# 06-General_I2C_Devices.net
KiCad netlist of a schematic drawn in Altium Designer
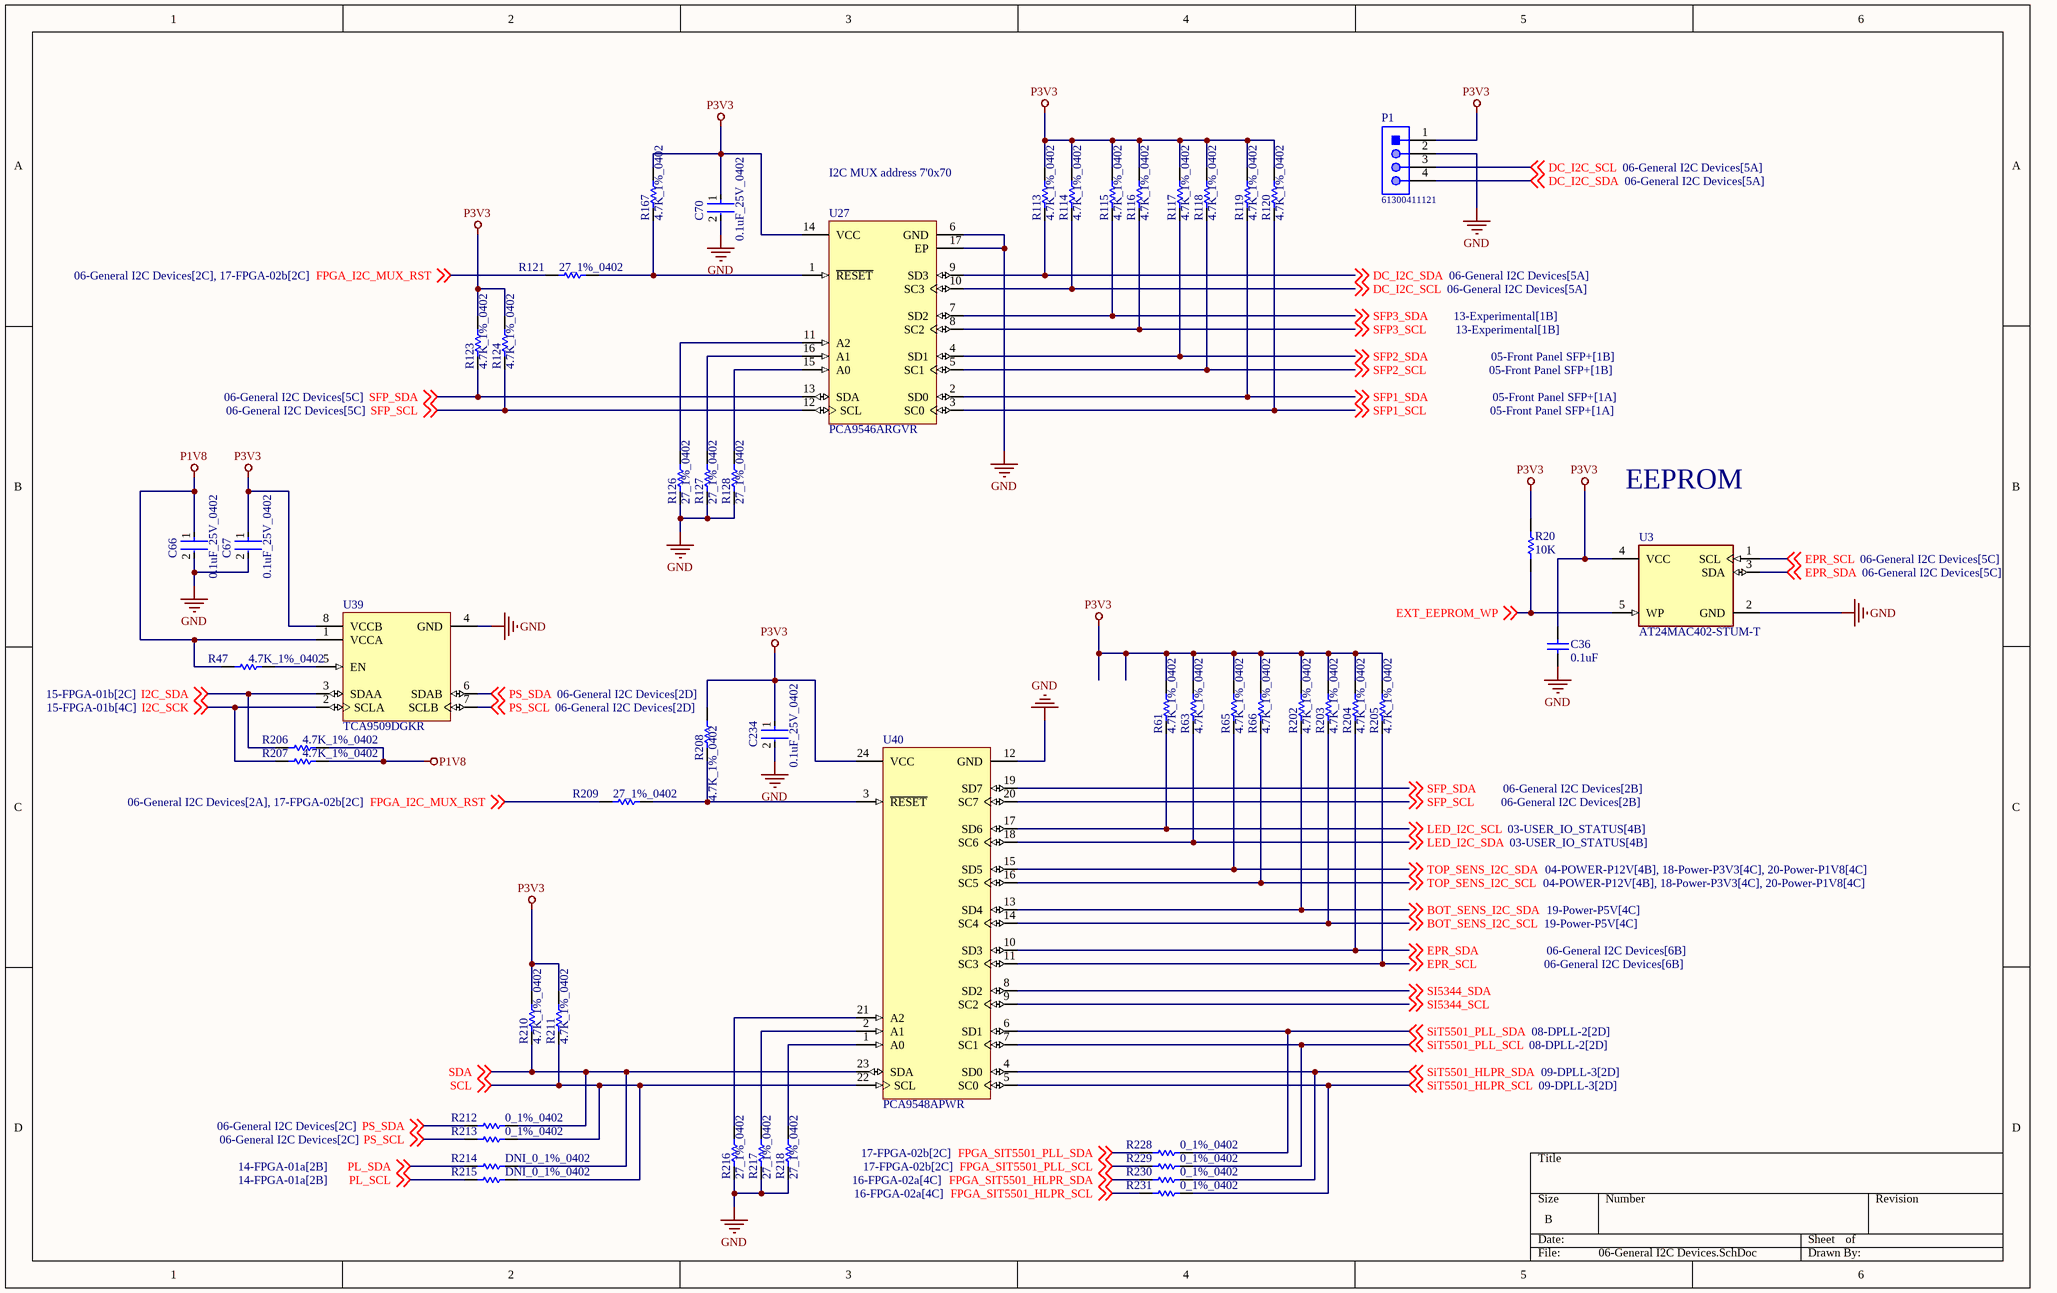
[diagram p0: 06-General I2C Devices.SchDoc]

(export (version "E")
  (design (tool "Eeschema 10.0.6"))
  (components
    (comp (ref "C36")
      (value "0.1uF")
      (footprint "CAPC1608X87X45ML20T05")
      (description "C0603X104K5RACAUTO")
      (fields (field (name "MANUFACTURER") "Kemet"))
      (libsource (lib "Altium Content Vault") (part "CAP"))
    )
    (comp (ref "C66")
      (value "0.1uF_25V_0402")
      (footprint "FP-0402-L_1_0_1-W_0_5_0_1-IPC_C")
      (description "General Purpose Ceramic Capacitor, 0402, 100nF, 10%, X7R, 15%, 25V")
      (fields (field (name "VOLTAGE") "25V") (field (name "TOLERANCE") "10%"))
      (libsource (lib "Altium Content Vault") (part "b4654b650e69147ec39a6b967a45e02"))
    )
    (comp (ref "C67")
      (value "0.1uF_25V_0402")
      (footprint "FP-0402-L_1_0_1-W_0_5_0_1-IPC_C")
      (description "General Purpose Ceramic Capacitor, 0402, 100nF, 10%, X7R, 15%, 25V")
      (fields (field (name "VOLTAGE") "25V") (field (name "TOLERANCE") "10%"))
      (libsource (lib "Altium Content Vault") (part "b4654b650e69147ec39a6b967a45e02"))
    )
    (comp (ref "C70")
      (value "0.1uF_25V_0402")
      (footprint "FP-0402-L_1_0_1-W_0_5_0_1-IPC_C")
      (description "General Purpose Ceramic Capacitor, 0402, 100nF, 10%, X7R, 15%, 25V")
      (fields (field (name "VOLTAGE") "25V") (field (name "TOLERANCE") "10%"))
      (libsource (lib "Altium Content Vault") (part "b4654b650e69147ec39a6b967a45e02"))
    )
    (comp (ref "C234")
      (value "0.1uF_25V_0402")
      (footprint "FP-0402-L_1_0_1-W_0_5_0_1-IPC_C")
      (description "General Purpose Ceramic Capacitor, 0402, 100nF, 10%, X7R, 15%, 25V")
      (fields (field (name "VOLTAGE") "25V") (field (name "TOLERANCE") "10%"))
      (libsource (lib "Altium Content Vault") (part "b4654b650e69147ec39a6b967a45e02"))
    )
    (comp (ref "P1")
      (value "61300411121")
      (footprint "61300411121")
      (description "THT Vertical Pin Header WR-PHD, Pitch 2.54 mm, Single Row, 4 pins")
      (fields (field (name "MANUFACTURER") "Wurth Elektronik") (field (name "PUBLISHER") "WurthElektronik"))
      (libsource (lib "Altium Content Vault") (part "WE-CN-1P-M-R4"))
    )
    (comp (ref "R20")
      (value "10K")
      (footprint "RESC1608X55X30LL15T20")
      (fields (field (name "TOLERANCE") "±1%") (field (name "MANUFACTURER") "Stackpole-Electronics-Inc."))
      (libsource (lib "Altium Content Vault") (part "RES-2"))
    )
    (comp (ref "R47")
      (value "4.7K_1%_0402")
      (footprint "RESC1005X40X25NL10T10")
      (fields (field (name "MANUFACTURER") "Bourns") (field (name "PART NUMBER") "CR0402-FX-4701GLF"))
      (libsource (lib "Altium Content Vault") (part "RES"))
    )
    (comp (ref "R61")
      (value "4.7K_1%_0402")
      (footprint "RESC1005X40X25NL10T10")
      (fields (field (name "MANUFACTURER") "Bourns") (field (name "PART NUMBER") "CR0402-FX-4701GLF"))
      (libsource (lib "Altium Content Vault") (part "RES"))
    )
    (comp (ref "R63")
      (value "4.7K_1%_0402")
      (footprint "RESC1005X40X25NL10T10")
      (fields (field (name "MANUFACTURER") "Bourns") (field (name "PART NUMBER") "CR0402-FX-4701GLF"))
      (libsource (lib "Altium Content Vault") (part "RES"))
    )
    (comp (ref "R65")
      (value "4.7K_1%_0402")
      (footprint "RESC1005X40X25NL10T10")
      (fields (field (name "MANUFACTURER") "Bourns") (field (name "PART NUMBER") "CR0402-FX-4701GLF"))
      (libsource (lib "Altium Content Vault") (part "RES"))
    )
    (comp (ref "R66")
      (value "4.7K_1%_0402")
      (footprint "RESC1005X40X25NL10T10")
      (fields (field (name "MANUFACTURER") "Bourns") (field (name "PART NUMBER") "CR0402-FX-4701GLF"))
      (libsource (lib "Altium Content Vault") (part "RES"))
    )
    (comp (ref "R113")
      (value "4.7K_1%_0402")
      (footprint "RESC1005X40X25NL10T10")
      (fields (field (name "MANUFACTURER") "Bourns") (field (name "PART NUMBER") "CR0402-FX-4701GLF"))
      (libsource (lib "Altium Content Vault") (part "RES"))
    )
    (comp (ref "R114")
      (value "4.7K_1%_0402")
      (footprint "RESC1005X40X25NL10T10")
      (fields (field (name "MANUFACTURER") "Bourns") (field (name "PART NUMBER") "CR0402-FX-4701GLF"))
      (libsource (lib "Altium Content Vault") (part "RES"))
    )
    (comp (ref "R115")
      (value "4.7K_1%_0402")
      (footprint "RESC1005X40X25NL10T10")
      (fields (field (name "MANUFACTURER") "Bourns") (field (name "PART NUMBER") "CR0402-FX-4701GLF"))
      (libsource (lib "Altium Content Vault") (part "RES"))
    )
    (comp (ref "R116")
      (value "4.7K_1%_0402")
      (footprint "RESC1005X40X25NL10T10")
      (fields (field (name "MANUFACTURER") "Bourns") (field (name "PART NUMBER") "CR0402-FX-4701GLF"))
      (libsource (lib "Altium Content Vault") (part "RES"))
    )
    (comp (ref "R117")
      (value "4.7K_1%_0402")
      (footprint "RESC1005X40X25NL10T10")
      (fields (field (name "MANUFACTURER") "Bourns") (field (name "PART NUMBER") "CR0402-FX-4701GLF"))
      (libsource (lib "Altium Content Vault") (part "RES"))
    )
    (comp (ref "R118")
      (value "4.7K_1%_0402")
      (footprint "RESC1005X40X25NL10T10")
      (fields (field (name "MANUFACTURER") "Bourns") (field (name "PART NUMBER") "CR0402-FX-4701GLF"))
      (libsource (lib "Altium Content Vault") (part "RES"))
    )
    (comp (ref "R119")
      (value "4.7K_1%_0402")
      (footprint "RESC1005X40X25NL10T10")
      (fields (field (name "MANUFACTURER") "Bourns") (field (name "PART NUMBER") "CR0402-FX-4701GLF"))
      (libsource (lib "Altium Content Vault") (part "RES"))
    )
    (comp (ref "R120")
      (value "4.7K_1%_0402")
      (footprint "RESC1005X40X25NL10T10")
      (fields (field (name "MANUFACTURER") "Bourns") (field (name "PART NUMBER") "CR0402-FX-4701GLF"))
      (libsource (lib "Altium Content Vault") (part "RES"))
    )
    (comp (ref "R121")
      (value "27_1%_0402")
      (footprint "RESC1005X40X25NL05T05")
      (fields (field (name "PART NUMBER") "CRCW040227R0FKED") (field (name "MANUFACTURER") "Vishay Dale"))
      (libsource (lib "Altium Content Vault") (part "RES"))
    )
    (comp (ref "R123")
      (value "4.7K_1%_0402")
      (footprint "RESC1005X40X25NL10T10")
      (fields (field (name "MANUFACTURER") "Bourns") (field (name "PART NUMBER") "CR0402-FX-4701GLF"))
      (libsource (lib "Altium Content Vault") (part "RES"))
    )
    (comp (ref "R124")
      (value "4.7K_1%_0402")
      (footprint "RESC1005X40X25NL10T10")
      (fields (field (name "MANUFACTURER") "Bourns") (field (name "PART NUMBER") "CR0402-FX-4701GLF"))
      (libsource (lib "Altium Content Vault") (part "RES"))
    )
    (comp (ref "R126")
      (value "27_1%_0402")
      (footprint "RESC1005X40X25NL05T05")
      (fields (field (name "PART NUMBER") "CRCW040227R0FKED") (field (name "MANUFACTURER") "Vishay Dale"))
      (libsource (lib "Altium Content Vault") (part "RES"))
    )
    (comp (ref "R127")
      (value "27_1%_0402")
      (footprint "RESC1005X40X25NL05T05")
      (fields (field (name "PART NUMBER") "CRCW040227R0FKED") (field (name "MANUFACTURER") "Vishay Dale"))
      (libsource (lib "Altium Content Vault") (part "RES"))
    )
    (comp (ref "R128")
      (value "27_1%_0402")
      (footprint "RESC1005X40X25NL05T05")
      (fields (field (name "PART NUMBER") "CRCW040227R0FKED") (field (name "MANUFACTURER") "Vishay Dale"))
      (libsource (lib "Altium Content Vault") (part "RES"))
    )
    (comp (ref "R167")
      (value "4.7K_1%_0402")
      (footprint "RESC1005X40X25NL10T10")
      (fields (field (name "MANUFACTURER") "Bourns") (field (name "PART NUMBER") "CR0402-FX-4701GLF"))
      (libsource (lib "Altium Content Vault") (part "RES"))
    )
    (comp (ref "R202")
      (value "4.7K_1%_0402")
      (footprint "RESC1005X40X25NL10T10")
      (fields (field (name "MANUFACTURER") "Bourns") (field (name "PART NUMBER") "CR0402-FX-4701GLF"))
      (libsource (lib "Altium Content Vault") (part "RES"))
    )
    (comp (ref "R203")
      (value "4.7K_1%_0402")
      (footprint "RESC1005X40X25NL10T10")
      (fields (field (name "MANUFACTURER") "Bourns") (field (name "PART NUMBER") "CR0402-FX-4701GLF"))
      (libsource (lib "Altium Content Vault") (part "RES"))
    )
    (comp (ref "R204")
      (value "4.7K_1%_0402")
      (footprint "RESC1005X40X25NL10T10")
      (fields (field (name "MANUFACTURER") "Bourns") (field (name "PART NUMBER") "CR0402-FX-4701GLF"))
      (libsource (lib "Altium Content Vault") (part "RES"))
    )
    (comp (ref "R205")
      (value "4.7K_1%_0402")
      (footprint "RESC1005X40X25NL10T10")
      (fields (field (name "MANUFACTURER") "Bourns") (field (name "PART NUMBER") "CR0402-FX-4701GLF"))
      (libsource (lib "Altium Content Vault") (part "RES"))
    )
    (comp (ref "R206")
      (value "4.7K_1%_0402")
      (footprint "RESC1005X40X25NL10T10")
      (fields (field (name "MANUFACTURER") "Bourns") (field (name "PART NUMBER") "CR0402-FX-4701GLF"))
      (libsource (lib "Altium Content Vault") (part "RES"))
    )
    (comp (ref "R207")
      (value "4.7K_1%_0402")
      (footprint "RESC1005X40X25NL10T10")
      (fields (field (name "MANUFACTURER") "Bourns") (field (name "PART NUMBER") "CR0402-FX-4701GLF"))
      (libsource (lib "Altium Content Vault") (part "RES"))
    )
    (comp (ref "R208")
      (value "4.7K_1%_0402")
      (footprint "RESC1005X40X25NL10T10")
      (fields (field (name "MANUFACTURER") "Bourns") (field (name "PART NUMBER") "CR0402-FX-4701GLF"))
      (libsource (lib "Altium Content Vault") (part "RES"))
    )
    (comp (ref "R209")
      (value "27_1%_0402")
      (footprint "RESC1005X40X25NL05T05")
      (fields (field (name "PART NUMBER") "CRCW040227R0FKED") (field (name "MANUFACTURER") "Vishay Dale"))
      (libsource (lib "Altium Content Vault") (part "RES"))
    )
    (comp (ref "R210")
      (value "4.7K_1%_0402")
      (footprint "RESC1005X40X25NL10T10")
      (fields (field (name "MANUFACTURER") "Bourns") (field (name "PART NUMBER") "CR0402-FX-4701GLF"))
      (libsource (lib "Altium Content Vault") (part "RES"))
    )
    (comp (ref "R211")
      (value "4.7K_1%_0402")
      (footprint "RESC1005X40X25NL10T10")
      (fields (field (name "MANUFACTURER") "Bourns") (field (name "PART NUMBER") "CR0402-FX-4701GLF"))
      (libsource (lib "Altium Content Vault") (part "RES"))
    )
    (comp (ref "R212")
      (value "0_1%_0402")
      (footprint "RESC1005X40X25LL05T05")
      (description "Chip Resistor, 0 Ohm, 0.1 W, -55 to 155 degC, 0402 (1005 Metric), RoHS, Tape and Reel")
      (fields (field (name "MANUFACTURER") "Panasonic") (field (name "TOLERANCE") "5%"))
      (libsource (lib "Altium Content Vault") (part "RES-2"))
    )
    (comp (ref "R213")
      (value "0_1%_0402")
      (footprint "RESC1005X40X25LL05T05")
      (description "Chip Resistor, 0 Ohm, 0.1 W, -55 to 155 degC, 0402 (1005 Metric), RoHS, Tape and Reel")
      (fields (field (name "MANUFACTURER") "Panasonic") (field (name "TOLERANCE") "5%"))
      (libsource (lib "Altium Content Vault") (part "RES-2"))
    )
    (comp (ref "R214")
      (value "DNI_0_1%_0402")
      (footprint "RESC1005X40X25LL05T05")
      (description "Chip Resistor, 0 Ohm, 0.1 W, -55 to 155 degC, 0402 (1005 Metric), RoHS, Tape and Reel")
      (fields (field (name "MANUFACTURER") "Panasonic") (field (name "TOLERANCE") "5%"))
      (libsource (lib "Altium Content Vault") (part "RES-2"))
    )
    (comp (ref "R215")
      (value "DNI_0_1%_0402")
      (footprint "RESC1005X40X25LL05T05")
      (description "Chip Resistor, 0 Ohm, 0.1 W, -55 to 155 degC, 0402 (1005 Metric), RoHS, Tape and Reel")
      (fields (field (name "MANUFACTURER") "Panasonic") (field (name "TOLERANCE") "5%"))
      (libsource (lib "Altium Content Vault") (part "RES-2"))
    )
    (comp (ref "R216")
      (value "27_1%_0402")
      (footprint "RESC1005X40X25NL05T05")
      (fields (field (name "PART NUMBER") "CRCW040227R0FKED") (field (name "MANUFACTURER") "Vishay Dale"))
      (libsource (lib "Altium Content Vault") (part "RES"))
    )
    (comp (ref "R217")
      (value "27_1%_0402")
      (footprint "RESC1005X40X25NL05T05")
      (fields (field (name "PART NUMBER") "CRCW040227R0FKED") (field (name "MANUFACTURER") "Vishay Dale"))
      (libsource (lib "Altium Content Vault") (part "RES"))
    )
    (comp (ref "R218")
      (value "27_1%_0402")
      (footprint "RESC1005X40X25NL05T05")
      (fields (field (name "PART NUMBER") "CRCW040227R0FKED") (field (name "MANUFACTURER") "Vishay Dale"))
      (libsource (lib "Altium Content Vault") (part "RES"))
    )
    (comp (ref "R228")
      (value "0_1%_0402")
      (footprint "RESC1005X40X25LL05T05")
      (description "Chip Resistor, 0 Ohm, 0.1 W, -55 to 155 degC, 0402 (1005 Metric), RoHS, Tape and Reel")
      (fields (field (name "MANUFACTURER") "Panasonic") (field (name "TOLERANCE") "5%"))
      (libsource (lib "Altium Content Vault") (part "RES-2"))
    )
    (comp (ref "R229")
      (value "0_1%_0402")
      (footprint "RESC1005X40X25LL05T05")
      (description "Chip Resistor, 0 Ohm, 0.1 W, -55 to 155 degC, 0402 (1005 Metric), RoHS, Tape and Reel")
      (fields (field (name "MANUFACTURER") "Panasonic") (field (name "TOLERANCE") "5%"))
      (libsource (lib "Altium Content Vault") (part "RES-2"))
    )
    (comp (ref "R230")
      (value "0_1%_0402")
      (footprint "RESC1005X40X25LL05T05")
      (description "Chip Resistor, 0 Ohm, 0.1 W, -55 to 155 degC, 0402 (1005 Metric), RoHS, Tape and Reel")
      (fields (field (name "MANUFACTURER") "Panasonic") (field (name "TOLERANCE") "5%"))
      (libsource (lib "Altium Content Vault") (part "RES-2"))
    )
    (comp (ref "R231")
      (value "0_1%_0402")
      (footprint "RESC1005X40X25LL05T05")
      (description "Chip Resistor, 0 Ohm, 0.1 W, -55 to 155 degC, 0402 (1005 Metric), RoHS, Tape and Reel")
      (fields (field (name "MANUFACTURER") "Panasonic") (field (name "TOLERANCE") "5%"))
      (libsource (lib "Altium Content Vault") (part "RES-2"))
    )
    (comp (ref "U3")
      (value "AT24MAC402-STUM-T")
      (footprint "FP-5TS1-IPC_C")
      (description "IC EEPROM 2K I2C 1MHZ SOT23-5")
      (fields
        (field (name "MANUFACTURER") "Microchip")
        (field (name "OCTOPART") "https://octopart.com/at24mac402-stum-t-microchip-77758112")
      )
      (libsource (lib "Altium Content Vault") (part "93fe34f5f049140596bab6421a6454b"))
    )
    (comp (ref "U27")
      (value "PCA9546ARGVR")
      (footprint "RGV0016A_V")
      (fields (field (name "MANUFACTURER") "Texas Instruments"))
      (libsource (lib "Altium Content Vault") (part "TI-PCA9546A-VQFN_RGV-16"))
    )
    (comp (ref "U39")
      (value "TCA9509DGKR")
      (footprint "DGK0008A_L")
      (fields (field (name "MANUFACTURER") "Texas Instruments"))
      (libsource (lib "Altium Content Vault") (part "TI-TCA9509-MSOP_DGK-8"))
    )
    (comp (ref "U40")
      (value "PCA9548APWR")
      (footprint "PW0024A_N")
      (fields (field (name "MANUFACTURER") "Texas Instruments"))
      (libsource (lib "Altium Content Vault") (part "TI-PCA9548A-TSSOP_PW-24"))
    )
  )
  (nets
    (net (code "1") (name "BOT_SENS_I2C_SCL") (class "Default")
      (node (ref "R203") (pin "1") (pinfunction "1_1") (pintype "passive"))
      (node (ref "U40") (pin "14") (pinfunction "SC4_14") (pintype "bidirectional"))
    )
    (net (code "2") (name "BOT_SENS_I2C_SDA") (class "Default")
      (node (ref "R202") (pin "1") (pinfunction "1_1") (pintype "passive"))
      (node (ref "U40") (pin "13") (pinfunction "SD4_13") (pintype "bidirectional"))
    )
    (net (code "3") (name "DC_I2C_SCL") (class "Default")
      (node (ref "P1") (pin "3") (pinfunction "3_3") (pintype "passive"))
      (node (ref "R114") (pin "1") (pinfunction "1_1") (pintype "passive"))
      (node (ref "U27") (pin "10") (pinfunction "SC3_10") (pintype "bidirectional"))
    )
    (net (code "4") (name "DC_I2C_SDA") (class "Default")
      (node (ref "P1") (pin "4") (pinfunction "4_4") (pintype "passive"))
      (node (ref "R113") (pin "1") (pinfunction "1_1") (pintype "passive"))
      (node (ref "U27") (pin "9") (pinfunction "SD3_9") (pintype "bidirectional"))
    )
    (net (code "5") (name "EPR_SCL") (class "Default")
      (node (ref "R205") (pin "1") (pinfunction "1_1") (pintype "passive"))
      (node (ref "U3") (pin "1") (pinfunction "SCL_1") (pintype "input"))
      (node (ref "U40") (pin "11") (pinfunction "SC3_11") (pintype "bidirectional"))
    )
    (net (code "6") (name "EPR_SDA") (class "Default")
      (node (ref "R204") (pin "1") (pinfunction "1_1") (pintype "passive"))
      (node (ref "U3") (pin "3") (pinfunction "SDA_3") (pintype "bidirectional"))
      (node (ref "U40") (pin "10") (pinfunction "SD3_10") (pintype "bidirectional"))
    )
    (net (code "7") (name "EXT_EEPROM_WP") (class "Default")
      (node (ref "R20") (pin "1") (pinfunction "1_1") (pintype "passive"))
      (node (ref "U3") (pin "5") (pinfunction "WP_5") (pintype "input"))
    )
    (net (code "8") (name "FPGA_I2C_MUX_RST") (class "Default")
      (node (ref "R121") (pin "1") (pinfunction "1_1") (pintype "passive"))
      (node (ref "R209") (pin "1") (pinfunction "1_1") (pintype "passive"))
    )
    (net (code "9") (name "FPGA_SIT5501_HLPR_SCL") (class "Default")
      (node (ref "R231") (pin "1") (pinfunction "1_1") (pintype "passive"))
    )
    (net (code "10") (name "FPGA_SIT5501_HLPR_SDA") (class "Default")
      (node (ref "R230") (pin "1") (pinfunction "1_1") (pintype "passive"))
    )
    (net (code "11") (name "FPGA_SIT5501_PLL_SCL") (class "Default")
      (node (ref "R229") (pin "1") (pinfunction "1_1") (pintype "passive"))
    )
    (net (code "12") (name "FPGA_SIT5501_PLL_SDA") (class "Default")
      (node (ref "R228") (pin "1") (pinfunction "1_1") (pintype "passive"))
    )
    (net (code "13") (name "GND") (class "Default")
      (node (ref "C234") (pin "2") (pinfunction "2_2") (pintype "passive"))
      (node (ref "C36") (pin "1") (pinfunction "1_1") (pintype "passive"))
      (node (ref "C66") (pin "2") (pinfunction "2_2") (pintype "passive"))
      (node (ref "C67") (pin "2") (pinfunction "2_2") (pintype "passive"))
      (node (ref "C70") (pin "2") (pinfunction "2_2") (pintype "passive"))
      (node (ref "P1") (pin "2") (pinfunction "2_2") (pintype "passive"))
      (node (ref "R126") (pin "1") (pinfunction "1_1") (pintype "passive"))
      (node (ref "R127") (pin "1") (pinfunction "1_1") (pintype "passive"))
      (node (ref "R128") (pin "1") (pinfunction "1_1") (pintype "passive"))
      (node (ref "R216") (pin "1") (pinfunction "1_1") (pintype "passive"))
      (node (ref "R217") (pin "1") (pinfunction "1_1") (pintype "passive"))
      (node (ref "R218") (pin "1") (pinfunction "1_1") (pintype "passive"))
      (node (ref "U27") (pin "17") (pinfunction "EP_17") (pintype "passive"))
      (node (ref "U27") (pin "6") (pinfunction "GND_6") (pintype "power_in"))
      (node (ref "U3") (pin "2") (pinfunction "GND_2") (pintype "power_in"))
      (node (ref "U39") (pin "4") (pinfunction "GND_4") (pintype "power_in"))
      (node (ref "U40") (pin "12") (pinfunction "GND_12") (pintype "power_in"))
    )
    (net (code "14") (name "I2C_SCK") (class "Default")
      (node (ref "R207") (pin "2") (pinfunction "2_2") (pintype "passive"))
      (node (ref "U39") (pin "2") (pinfunction "SCLA_2") (pintype "bidirectional"))
    )
    (net (code "15") (name "I2C_SDA") (class "Default")
      (node (ref "R206") (pin "2") (pinfunction "2_2") (pintype "passive"))
      (node (ref "U39") (pin "3") (pinfunction "SDAA_3") (pintype "bidirectional"))
    )
    (net (code "16") (name "LED_I2C_SCL") (class "Default")
      (node (ref "R61") (pin "1") (pinfunction "1_1") (pintype "passive"))
      (node (ref "U40") (pin "17") (pinfunction "SD6_17") (pintype "bidirectional"))
    )
    (net (code "17") (name "LED_I2C_SDA") (class "Default")
      (node (ref "R63") (pin "1") (pinfunction "1_1") (pintype "passive"))
      (node (ref "U40") (pin "18") (pinfunction "SC6_18") (pintype "bidirectional"))
    )
    (net (code "18") (name "Net-(U27-A0)") (class "Default")
      (node (ref "R128") (pin "2") (pinfunction "2_2") (pintype "passive"))
      (node (ref "U27") (pin "15") (pinfunction "A0_15") (pintype "input"))
    )
    (net (code "19") (name "Net-(U27-A1)") (class "Default")
      (node (ref "R127") (pin "2") (pinfunction "2_2") (pintype "passive"))
      (node (ref "U27") (pin "16") (pinfunction "A1_16") (pintype "input"))
    )
    (net (code "20") (name "Net-(U27-A2)") (class "Default")
      (node (ref "R126") (pin "2") (pinfunction "2_2") (pintype "passive"))
      (node (ref "U27") (pin "11") (pinfunction "A2_11") (pintype "input"))
    )
    (net (code "21") (name "Net-(U27-~{RESET})") (class "Default")
      (node (ref "R121") (pin "2") (pinfunction "2_2") (pintype "passive"))
      (node (ref "R167") (pin "1") (pinfunction "1_1") (pintype "passive"))
      (node (ref "U27") (pin "1") (pinfunction "~{RESET}_1") (pintype "input"))
    )
    (net (code "22") (name "Net-(U39-EN)") (class "Default")
      (node (ref "R47") (pin "1") (pinfunction "1_1") (pintype "passive"))
      (node (ref "U39") (pin "5") (pinfunction "EN_5") (pintype "input"))
    )
    (net (code "23") (name "Net-(U40-A0)") (class "Default")
      (node (ref "R218") (pin "2") (pinfunction "2_2") (pintype "passive"))
      (node (ref "U40") (pin "1") (pinfunction "A0_1") (pintype "input"))
    )
    (net (code "24") (name "Net-(U40-A1)") (class "Default")
      (node (ref "R217") (pin "2") (pinfunction "2_2") (pintype "passive"))
      (node (ref "U40") (pin "2") (pinfunction "A1_2") (pintype "input"))
    )
    (net (code "25") (name "Net-(U40-A2)") (class "Default")
      (node (ref "R216") (pin "2") (pinfunction "2_2") (pintype "passive"))
      (node (ref "U40") (pin "21") (pinfunction "A2_21") (pintype "input"))
    )
    (net (code "26") (name "Net-(U40-~{RESET})") (class "Default")
      (node (ref "R208") (pin "1") (pinfunction "1_1") (pintype "passive"))
      (node (ref "R209") (pin "2") (pinfunction "2_2") (pintype "passive"))
      (node (ref "U40") (pin "3") (pinfunction "~{RESET}_3") (pintype "input"))
    )
    (net (code "27") (name "P1V8") (class "Default")
      (node (ref "C66") (pin "1") (pinfunction "1_1") (pintype "passive"))
      (node (ref "R206") (pin "1") (pinfunction "1_1") (pintype "passive"))
      (node (ref "R207") (pin "1") (pinfunction "1_1") (pintype "passive"))
      (node (ref "R47") (pin "2") (pinfunction "2_2") (pintype "passive"))
      (node (ref "U39") (pin "1") (pinfunction "VCCA_1") (pintype "power_in"))
    )
    (net (code "28") (name "P3V3") (class "Default")
      (node (ref "C234") (pin "1") (pinfunction "1_1") (pintype "passive"))
      (node (ref "C36") (pin "2") (pinfunction "2_2") (pintype "passive"))
      (node (ref "C67") (pin "1") (pinfunction "1_1") (pintype "passive"))
      (node (ref "C70") (pin "1") (pinfunction "1_1") (pintype "passive"))
      (node (ref "P1") (pin "1") (pinfunction "1_1") (pintype "passive"))
      (node (ref "R113") (pin "2") (pinfunction "2_2") (pintype "passive"))
      (node (ref "R114") (pin "2") (pinfunction "2_2") (pintype "passive"))
      (node (ref "R115") (pin "2") (pinfunction "2_2") (pintype "passive"))
      (node (ref "R116") (pin "2") (pinfunction "2_2") (pintype "passive"))
      (node (ref "R117") (pin "2") (pinfunction "2_2") (pintype "passive"))
      (node (ref "R118") (pin "2") (pinfunction "2_2") (pintype "passive"))
      (node (ref "R119") (pin "2") (pinfunction "2_2") (pintype "passive"))
      (node (ref "R120") (pin "2") (pinfunction "2_2") (pintype "passive"))
      (node (ref "R123") (pin "2") (pinfunction "2_2") (pintype "passive"))
      (node (ref "R124") (pin "2") (pinfunction "2_2") (pintype "passive"))
      (node (ref "R167") (pin "2") (pinfunction "2_2") (pintype "passive"))
      (node (ref "R20") (pin "2") (pinfunction "2_2") (pintype "passive"))
      (node (ref "R202") (pin "2") (pinfunction "2_2") (pintype "passive"))
      (node (ref "R203") (pin "2") (pinfunction "2_2") (pintype "passive"))
      (node (ref "R204") (pin "2") (pinfunction "2_2") (pintype "passive"))
      (node (ref "R205") (pin "2") (pinfunction "2_2") (pintype "passive"))
      (node (ref "R208") (pin "2") (pinfunction "2_2") (pintype "passive"))
      (node (ref "R210") (pin "2") (pinfunction "2_2") (pintype "passive"))
      (node (ref "R211") (pin "2") (pinfunction "2_2") (pintype "passive"))
      (node (ref "R61") (pin "2") (pinfunction "2_2") (pintype "passive"))
      (node (ref "R63") (pin "2") (pinfunction "2_2") (pintype "passive"))
      (node (ref "R65") (pin "2") (pinfunction "2_2") (pintype "passive"))
      (node (ref "R66") (pin "2") (pinfunction "2_2") (pintype "passive"))
      (node (ref "U27") (pin "14") (pinfunction "VCC_14") (pintype "power_in"))
      (node (ref "U3") (pin "4") (pinfunction "VCC_4") (pintype "power_in"))
      (node (ref "U39") (pin "8") (pinfunction "VCCB_8") (pintype "power_in"))
      (node (ref "U40") (pin "24") (pinfunction "VCC_24") (pintype "power_in"))
    )
    (net (code "29") (name "PL_SCL") (class "Default")
      (node (ref "R215") (pin "1") (pinfunction "1_1") (pintype "passive"))
    )
    (net (code "30") (name "PL_SDA") (class "Default")
      (node (ref "R214") (pin "1") (pinfunction "1_1") (pintype "passive"))
    )
    (net (code "31") (name "PS_SCL") (class "Default")
      (node (ref "R213") (pin "1") (pinfunction "1_1") (pintype "passive"))
      (node (ref "U39") (pin "7") (pinfunction "SCLB_7") (pintype "bidirectional"))
    )
    (net (code "32") (name "PS_SDA") (class "Default")
      (node (ref "R212") (pin "1") (pinfunction "1_1") (pintype "passive"))
      (node (ref "U39") (pin "6") (pinfunction "SDAB_6") (pintype "bidirectional"))
    )
    (net (code "33") (name "SCL") (class "Default")
      (node (ref "R211") (pin "1") (pinfunction "1_1") (pintype "passive"))
      (node (ref "R213") (pin "2") (pinfunction "2_2") (pintype "passive"))
      (node (ref "R215") (pin "2") (pinfunction "2_2") (pintype "passive"))
      (node (ref "U40") (pin "22") (pinfunction "SCL_22") (pintype "input"))
    )
    (net (code "34") (name "SDA") (class "Default")
      (node (ref "R210") (pin "1") (pinfunction "1_1") (pintype "passive"))
      (node (ref "R212") (pin "2") (pinfunction "2_2") (pintype "passive"))
      (node (ref "R214") (pin "2") (pinfunction "2_2") (pintype "passive"))
      (node (ref "U40") (pin "23") (pinfunction "SDA_23") (pintype "bidirectional"))
    )
    (net (code "35") (name "SFP1_SCL") (class "Default")
      (node (ref "R120") (pin "1") (pinfunction "1_1") (pintype "passive"))
      (node (ref "U27") (pin "3") (pinfunction "SC0_3") (pintype "bidirectional"))
    )
    (net (code "36") (name "SFP1_SDA") (class "Default")
      (node (ref "R119") (pin "1") (pinfunction "1_1") (pintype "passive"))
      (node (ref "U27") (pin "2") (pinfunction "SD0_2") (pintype "bidirectional"))
    )
    (net (code "37") (name "SFP2_SCL") (class "Default")
      (node (ref "R118") (pin "1") (pinfunction "1_1") (pintype "passive"))
      (node (ref "U27") (pin "5") (pinfunction "SC1_5") (pintype "bidirectional"))
    )
    (net (code "38") (name "SFP2_SDA") (class "Default")
      (node (ref "R117") (pin "1") (pinfunction "1_1") (pintype "passive"))
      (node (ref "U27") (pin "4") (pinfunction "SD1_4") (pintype "bidirectional"))
    )
    (net (code "39") (name "SFP3_SCL") (class "Default")
      (node (ref "R116") (pin "1") (pinfunction "1_1") (pintype "passive"))
      (node (ref "U27") (pin "8") (pinfunction "SC2_8") (pintype "bidirectional"))
    )
    (net (code "40") (name "SFP3_SDA") (class "Default")
      (node (ref "R115") (pin "1") (pinfunction "1_1") (pintype "passive"))
      (node (ref "U27") (pin "7") (pinfunction "SD2_7") (pintype "bidirectional"))
    )
    (net (code "41") (name "SFP_SCL") (class "Default")
      (node (ref "R124") (pin "1") (pinfunction "1_1") (pintype "passive"))
      (node (ref "U27") (pin "12") (pinfunction "SCL_12") (pintype "bidirectional"))
      (node (ref "U40") (pin "20") (pinfunction "SC7_20") (pintype "bidirectional"))
    )
    (net (code "42") (name "SFP_SDA") (class "Default")
      (node (ref "R123") (pin "1") (pinfunction "1_1") (pintype "passive"))
      (node (ref "U27") (pin "13") (pinfunction "SDA_13") (pintype "bidirectional"))
      (node (ref "U40") (pin "19") (pinfunction "SD7_19") (pintype "bidirectional"))
    )
    (net (code "43") (name "SI5344_SCL") (class "Default")
      (node (ref "U40") (pin "9") (pinfunction "SC2_9") (pintype "bidirectional"))
    )
    (net (code "44") (name "SI5344_SDA") (class "Default")
      (node (ref "U40") (pin "8") (pinfunction "SD2_8") (pintype "bidirectional"))
    )
    (net (code "45") (name "SiT5501_HLPR_SCL") (class "Default")
      (node (ref "R231") (pin "2") (pinfunction "2_2") (pintype "passive"))
      (node (ref "U40") (pin "5") (pinfunction "SC0_5") (pintype "bidirectional"))
    )
    (net (code "46") (name "SiT5501_HLPR_SDA") (class "Default")
      (node (ref "R230") (pin "2") (pinfunction "2_2") (pintype "passive"))
      (node (ref "U40") (pin "4") (pinfunction "SD0_4") (pintype "bidirectional"))
    )
    (net (code "47") (name "SiT5501_PLL_SCL") (class "Default")
      (node (ref "R229") (pin "2") (pinfunction "2_2") (pintype "passive"))
      (node (ref "U40") (pin "7") (pinfunction "SC1_7") (pintype "bidirectional"))
    )
    (net (code "48") (name "SiT5501_PLL_SDA") (class "Default")
      (node (ref "R228") (pin "2") (pinfunction "2_2") (pintype "passive"))
      (node (ref "U40") (pin "6") (pinfunction "SD1_6") (pintype "bidirectional"))
    )
    (net (code "49") (name "TOP_SENS_I2C_SCL") (class "Default")
      (node (ref "R66") (pin "1") (pinfunction "1_1") (pintype "passive"))
      (node (ref "U40") (pin "16") (pinfunction "SC5_16") (pintype "bidirectional"))
    )
    (net (code "50") (name "TOP_SENS_I2C_SDA") (class "Default")
      (node (ref "R65") (pin "1") (pinfunction "1_1") (pintype "passive"))
      (node (ref "U40") (pin "15") (pinfunction "SD5_15") (pintype "bidirectional"))
    )
  )
)
